# 09_FPGA_banks_5_6_7_8.net
KiCad netlist of a schematic drawn in Altium Designer
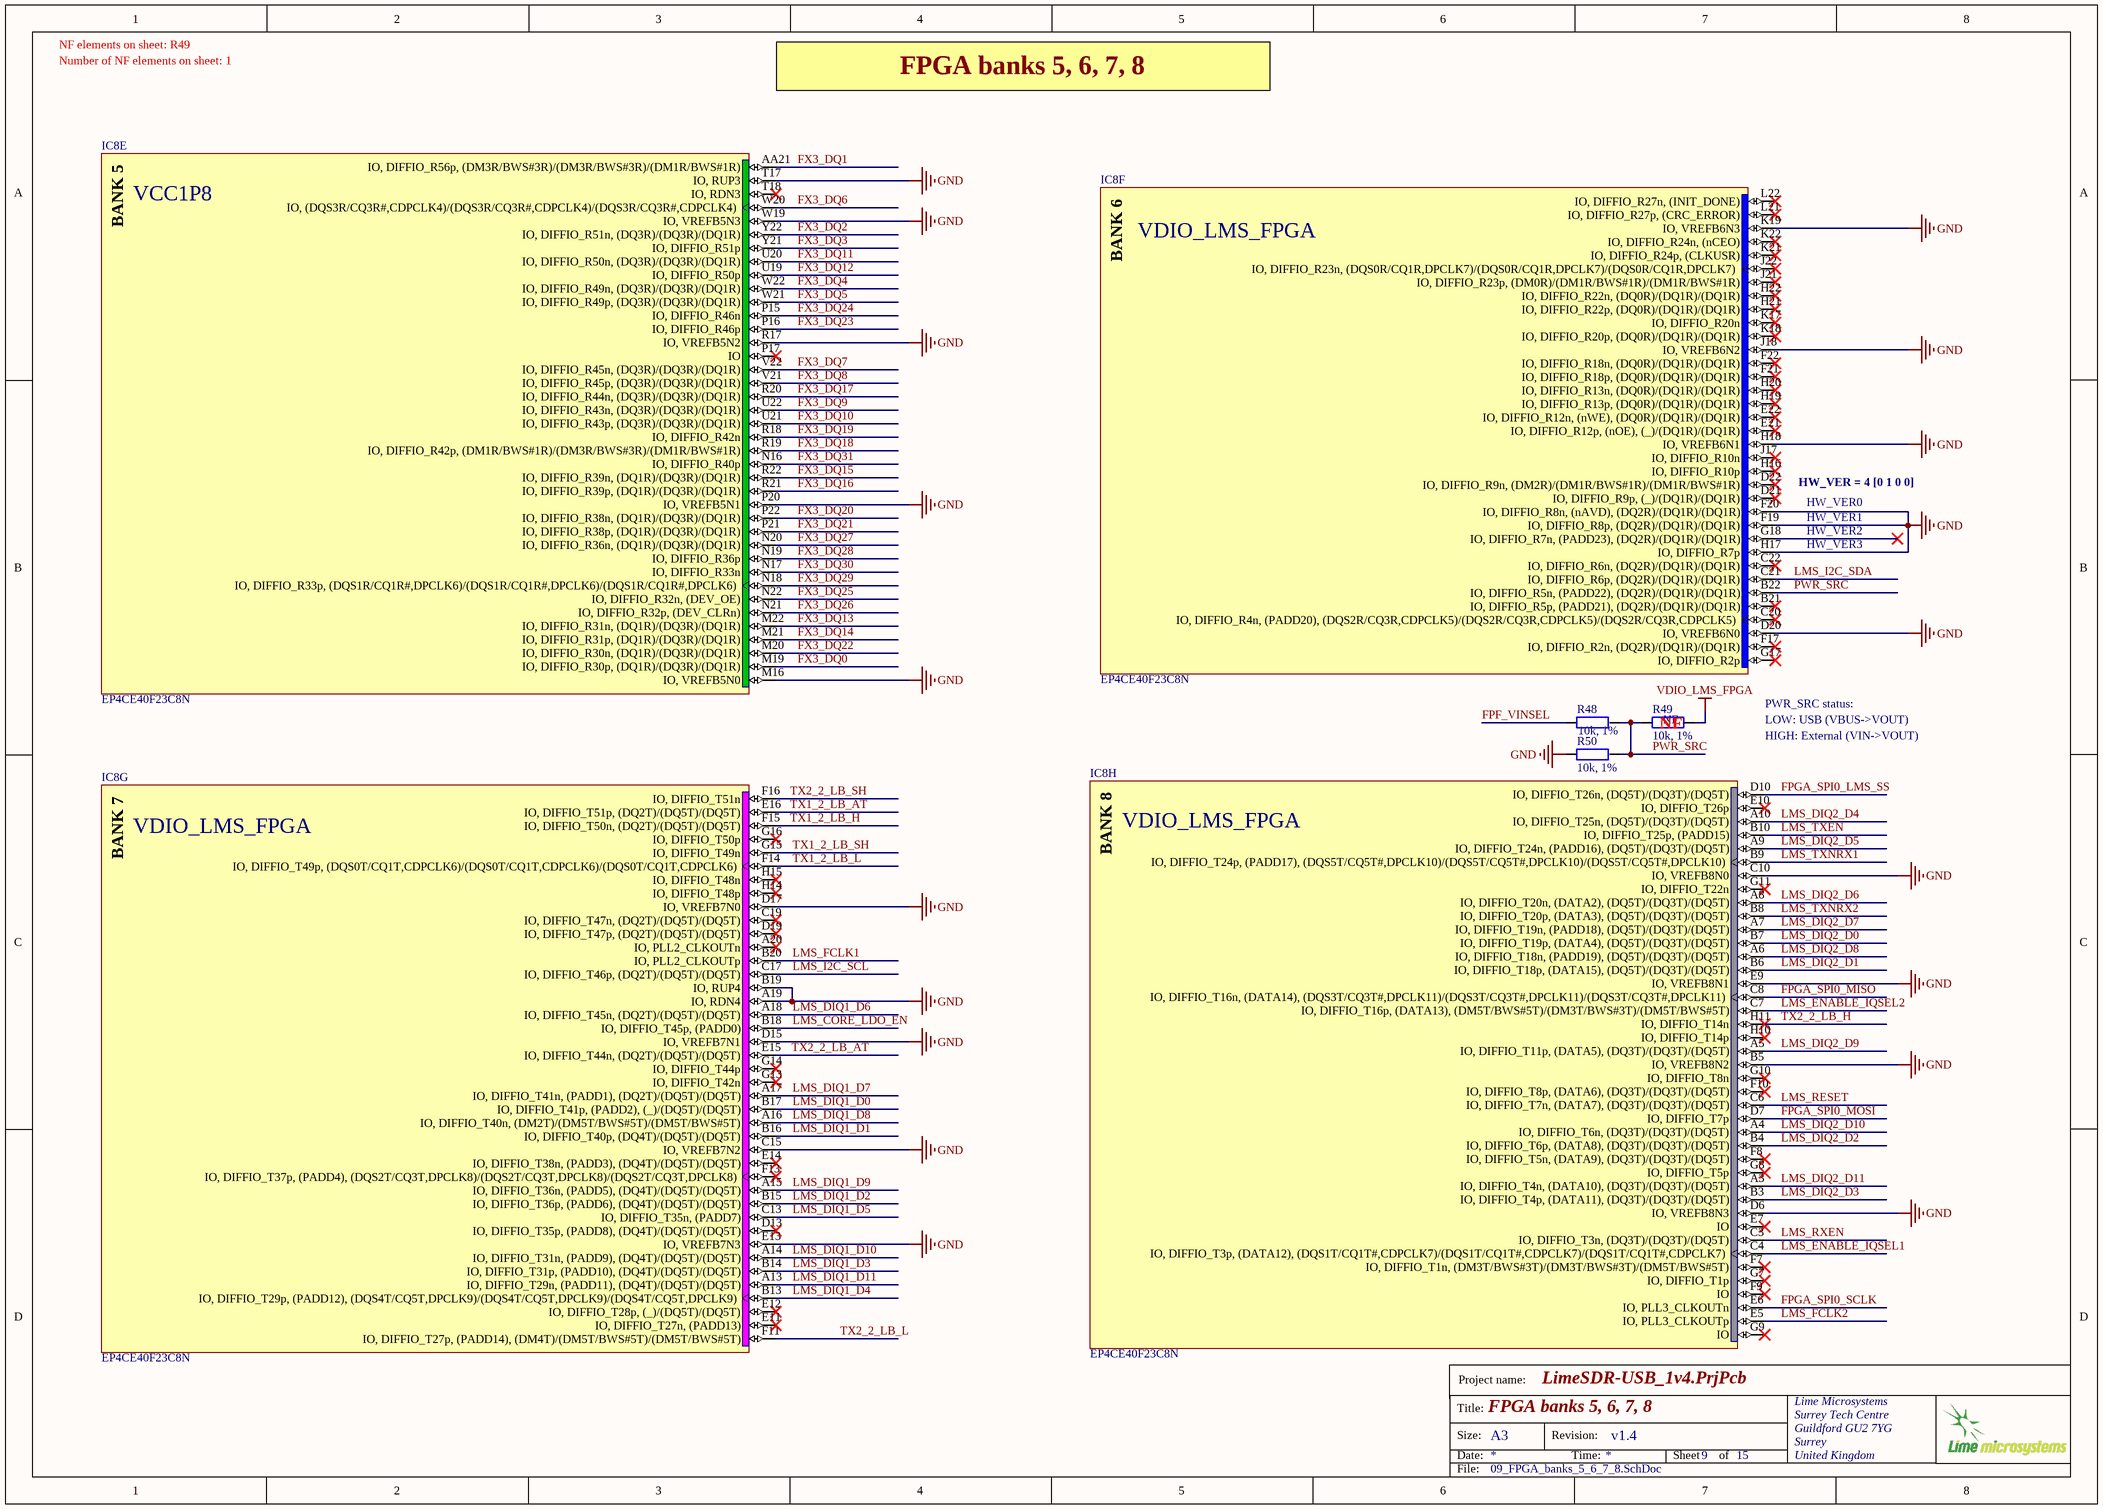
[diagram p0: 09_FPGA_banks_5_6_7_8.SchDoc]

(export (version "E")
  (design (tool "Eeschema 10.0.6"))
  (components
    (comp (ref "IC8")
      (value "EP4CE40F23C8N")
      (footprint "FBGA484_A-240")
      (description "IC FPGA 328 I/O 484FBGA")
      (fields (field (name "MANUFACTURER") "Altera"))
      (libsource (lib "LimeMicroAltiumLib_schLib") (part "EP4CE40F23C7N"))
    )
    (comp (ref "R48")
      (value "10k, 1%")
      (footprint "RES0402")
      (fields (field (name "MANUFACTURER") "Yageo") (field (name "TOLERANCE") "±1%"))
      (libsource (lib "LimeMicroAltiumLib_schLib") (part "Res_0402"))
    )
    (comp (ref "R49")
      (value "10k, 1%")
      (footprint "RES0402")
      (fields
        (field (name "ASSEMBLY INFO") "NF")
        (field (name "MANUFACTURER") "Yageo")
        (field (name "TOLERANCE") "±1%")
      )
      (libsource (lib "LimeMicroAltiumLib_schLib") (part "Res_0402"))
    )
    (comp (ref "R50")
      (value "10k, 1%")
      (footprint "RES0402")
      (fields (field (name "MANUFACTURER") "Yageo") (field (name "TOLERANCE") "±1%"))
      (libsource (lib "LimeMicroAltiumLib_schLib") (part "Res_0402"))
    )
  )
  (nets
    (net (code "1") (name "/FPF_VINSEL") (class "Default")
      (node (ref "R48") (pin "1") (pinfunction "1_1") (pintype "passive"))
    )
    (net (code "2") (name "/FPGA_SPI0_LMS_SS") (class "Default")
      (node (ref "IC8") (pin "D10") (pinfunction "IO,_DIFFIO_T26n,_(DQ5T)/(DQ3T)/(DQ5T)_D10") (pintype "bidirectional"))
    )
    (net (code "3") (name "/FPGA_SPI0_MISO") (class "Default")
      (node (ref "IC8") (pin "C8") (pinfunction "IO,_DIFFIO_T16n,_(DATA14),_(DQS3T/CQ3T#,DPCLK11)/(DQS3T/CQ3T#,DPCLK11)/(DQS3T/CQ3T#,DPCLK11)_C8") (pintype "bidirectional"))
    )
    (net (code "4") (name "/FPGA_SPI0_MOSI") (class "Default")
      (node (ref "IC8") (pin "D7") (pinfunction "IO,_DIFFIO_T7p_D7") (pintype "bidirectional"))
    )
    (net (code "5") (name "/FPGA_SPI0_SCLK") (class "Default")
      (node (ref "IC8") (pin "E6") (pinfunction "IO,_PLL3_CLKOUTn_E6") (pintype "bidirectional"))
    )
    (net (code "6") (name "/FX3_DQ0") (class "Default")
      (node (ref "IC8") (pin "M19") (pinfunction "IO,_DIFFIO_R30p,_(DQ1R)/(DQ3R)/(DQ1R)_M19") (pintype "bidirectional"))
    )
    (net (code "7") (name "/FX3_DQ1") (class "Default")
      (node (ref "IC8") (pin "AA21") (pinfunction "IO,_DIFFIO_R56p,_(DM3R/BWS#3R)/(DM3R/BWS#3R)/(DM1R/BWS#1R)_AA21") (pintype "bidirectional"))
    )
    (net (code "8") (name "/FX3_DQ2") (class "Default")
      (node (ref "IC8") (pin "Y22") (pinfunction "IO,_DIFFIO_R51n,_(DQ3R)/(DQ3R)/(DQ1R)_Y22") (pintype "bidirectional"))
    )
    (net (code "9") (name "/FX3_DQ3") (class "Default")
      (node (ref "IC8") (pin "Y21") (pinfunction "IO,_DIFFIO_R51p_Y21") (pintype "bidirectional"))
    )
    (net (code "10") (name "/FX3_DQ4") (class "Default")
      (node (ref "IC8") (pin "W22") (pinfunction "IO,_DIFFIO_R49n,_(DQ3R)/(DQ3R)/(DQ1R)_W22") (pintype "bidirectional"))
    )
    (net (code "11") (name "/FX3_DQ5") (class "Default")
      (node (ref "IC8") (pin "W21") (pinfunction "IO,_DIFFIO_R49p,_(DQ3R)/(DQ3R)/(DQ1R)_W21") (pintype "bidirectional"))
    )
    (net (code "12") (name "/FX3_DQ6") (class "Default")
      (node (ref "IC8") (pin "W20") (pinfunction "IO,_(DQS3R/CQ3R#,CDPCLK4)/(DQS3R/CQ3R#,CDPCLK4)/(DQS3R/CQ3R#,CDPCLK4)_W20") (pintype "bidirectional"))
    )
    (net (code "13") (name "/FX3_DQ7") (class "Default")
      (node (ref "IC8") (pin "V22") (pinfunction "IO,_DIFFIO_R45n,_(DQ3R)/(DQ3R)/(DQ1R)_V22") (pintype "bidirectional"))
    )
    (net (code "14") (name "/FX3_DQ8") (class "Default")
      (node (ref "IC8") (pin "V21") (pinfunction "IO,_DIFFIO_R45p,_(DQ3R)/(DQ3R)/(DQ1R)_V21") (pintype "bidirectional"))
    )
    (net (code "15") (name "/FX3_DQ9") (class "Default")
      (node (ref "IC8") (pin "U22") (pinfunction "IO,_DIFFIO_R43n,_(DQ3R)/(DQ3R)/(DQ1R)_U22") (pintype "bidirectional"))
    )
    (net (code "16") (name "/FX3_DQ10") (class "Default")
      (node (ref "IC8") (pin "U21") (pinfunction "IO,_DIFFIO_R43p,_(DQ3R)/(DQ3R)/(DQ1R)_U21") (pintype "bidirectional"))
    )
    (net (code "17") (name "/FX3_DQ11") (class "Default")
      (node (ref "IC8") (pin "U20") (pinfunction "IO,_DIFFIO_R50n,_(DQ3R)/(DQ3R)/(DQ1R)_U20") (pintype "bidirectional"))
    )
    (net (code "18") (name "/FX3_DQ12") (class "Default")
      (node (ref "IC8") (pin "U19") (pinfunction "IO,_DIFFIO_R50p_U19") (pintype "bidirectional"))
    )
    (net (code "19") (name "/FX3_DQ13") (class "Default")
      (node (ref "IC8") (pin "M22") (pinfunction "IO,_DIFFIO_R31n,_(DQ1R)/(DQ3R)/(DQ1R)_M22") (pintype "bidirectional"))
    )
    (net (code "20") (name "/FX3_DQ14") (class "Default")
      (node (ref "IC8") (pin "M21") (pinfunction "IO,_DIFFIO_R31p,_(DQ1R)/(DQ3R)/(DQ1R)_M21") (pintype "bidirectional"))
    )
    (net (code "21") (name "/FX3_DQ15") (class "Default")
      (node (ref "IC8") (pin "R22") (pinfunction "IO,_DIFFIO_R39n,_(DQ1R)/(DQ3R)/(DQ1R)_R22") (pintype "bidirectional"))
    )
    (net (code "22") (name "/FX3_DQ16") (class "Default")
      (node (ref "IC8") (pin "R21") (pinfunction "IO,_DIFFIO_R39p,_(DQ1R)/(DQ3R)/(DQ1R)_R21") (pintype "bidirectional"))
    )
    (net (code "23") (name "/FX3_DQ17") (class "Default")
      (node (ref "IC8") (pin "R20") (pinfunction "IO,_DIFFIO_R44n,_(DQ3R)/(DQ3R)/(DQ1R)_R20") (pintype "bidirectional"))
    )
    (net (code "24") (name "/FX3_DQ18") (class "Default")
      (node (ref "IC8") (pin "R19") (pinfunction "IO,_DIFFIO_R42p,_(DM1R/BWS#1R)/(DM3R/BWS#3R)/(DM1R/BWS#1R)_R19") (pintype "bidirectional"))
    )
    (net (code "25") (name "/FX3_DQ19") (class "Default")
      (node (ref "IC8") (pin "R18") (pinfunction "IO,_DIFFIO_R42n_R18") (pintype "bidirectional"))
    )
    (net (code "26") (name "/FX3_DQ20") (class "Default")
      (node (ref "IC8") (pin "P22") (pinfunction "IO,_DIFFIO_R38n,_(DQ1R)/(DQ3R)/(DQ1R)_P22") (pintype "bidirectional"))
    )
    (net (code "27") (name "/FX3_DQ21") (class "Default")
      (node (ref "IC8") (pin "P21") (pinfunction "IO,_DIFFIO_R38p,_(DQ1R)/(DQ3R)/(DQ1R)_P21") (pintype "bidirectional"))
    )
    (net (code "28") (name "/FX3_DQ22") (class "Default")
      (node (ref "IC8") (pin "M20") (pinfunction "IO,_DIFFIO_R30n,_(DQ1R)/(DQ3R)/(DQ1R)_M20") (pintype "bidirectional"))
    )
    (net (code "29") (name "/FX3_DQ23") (class "Default")
      (node (ref "IC8") (pin "P16") (pinfunction "IO,_DIFFIO_R46p_P16") (pintype "bidirectional"))
    )
    (net (code "30") (name "/FX3_DQ24") (class "Default")
      (node (ref "IC8") (pin "P15") (pinfunction "IO,_DIFFIO_R46n_P15") (pintype "bidirectional"))
    )
    (net (code "31") (name "/FX3_DQ25") (class "Default")
      (node (ref "IC8") (pin "N22") (pinfunction "IO,_DIFFIO_R32n,_(DEV_OE)_N22") (pintype "bidirectional"))
    )
    (net (code "32") (name "/FX3_DQ26") (class "Default")
      (node (ref "IC8") (pin "N21") (pinfunction "IO,_DIFFIO_R32p,_(DEV_CLRn)_N21") (pintype "bidirectional"))
    )
    (net (code "33") (name "/FX3_DQ27") (class "Default")
      (node (ref "IC8") (pin "N20") (pinfunction "IO,_DIFFIO_R36n,_(DQ1R)/(DQ3R)/(DQ1R)_N20") (pintype "bidirectional"))
    )
    (net (code "34") (name "/FX3_DQ28") (class "Default")
      (node (ref "IC8") (pin "N19") (pinfunction "IO,_DIFFIO_R36p_N19") (pintype "bidirectional"))
    )
    (net (code "35") (name "/FX3_DQ29") (class "Default")
      (node (ref "IC8") (pin "N18") (pinfunction "IO,_DIFFIO_R33p,_(DQS1R/CQ1R#,DPCLK6)/(DQS1R/CQ1R#,DPCLK6)/(DQS1R/CQ1R#,DPCLK6)_N18") (pintype "bidirectional"))
    )
    (net (code "36") (name "/FX3_DQ30") (class "Default")
      (node (ref "IC8") (pin "N17") (pinfunction "IO,_DIFFIO_R33n_N17") (pintype "bidirectional"))
    )
    (net (code "37") (name "/FX3_DQ31") (class "Default")
      (node (ref "IC8") (pin "N16") (pinfunction "IO,_DIFFIO_R40p_N16") (pintype "bidirectional"))
    )
    (net (code "38") (name "/LMS_CORE_LDO_EN") (class "Default")
      (node (ref "IC8") (pin "B18") (pinfunction "IO,_DIFFIO_T45p,_(PADD0)_B18") (pintype "bidirectional"))
    )
    (net (code "39") (name "/LMS_DIQ1_D0") (class "Default")
      (node (ref "IC8") (pin "B17") (pinfunction "IO,_DIFFIO_T41p,_(PADD2),_(_)/(DQ5T)/(DQ5T)_B17") (pintype "bidirectional"))
    )
    (net (code "40") (name "/LMS_DIQ1_D1") (class "Default")
      (node (ref "IC8") (pin "B16") (pinfunction "IO,_DIFFIO_T40p,_(DQ4T)/(DQ5T)/(DQ5T)_B16") (pintype "bidirectional"))
    )
    (net (code "41") (name "/LMS_DIQ1_D2") (class "Default")
      (node (ref "IC8") (pin "B15") (pinfunction "IO,_DIFFIO_T36p,_(PADD6),_(DQ4T)/(DQ5T)/(DQ5T)_B15") (pintype "bidirectional"))
    )
    (net (code "42") (name "/LMS_DIQ1_D3") (class "Default")
      (node (ref "IC8") (pin "B14") (pinfunction "IO,_DIFFIO_T31p,_(PADD10),_(DQ4T)/(DQ5T)/(DQ5T)_B14") (pintype "bidirectional"))
    )
    (net (code "43") (name "/LMS_DIQ1_D4") (class "Default")
      (node (ref "IC8") (pin "B13") (pinfunction "IO,_DIFFIO_T29p,_(PADD12),_(DQS4T/CQ5T,DPCLK9)/(DQS4T/CQ5T,DPCLK9)/(DQS4T/CQ5T,DPCLK9)_B13") (pintype "bidirectional"))
    )
    (net (code "44") (name "/LMS_DIQ1_D5") (class "Default")
      (node (ref "IC8") (pin "C13") (pinfunction "IO,_DIFFIO_T35n,_(PADD7)_C13") (pintype "bidirectional"))
    )
    (net (code "45") (name "/LMS_DIQ1_D6") (class "Default")
      (node (ref "IC8") (pin "A18") (pinfunction "IO,_DIFFIO_T45n,_(DQ2T)/(DQ5T)/(DQ5T)_A18") (pintype "bidirectional"))
    )
    (net (code "46") (name "/LMS_DIQ1_D7") (class "Default")
      (node (ref "IC8") (pin "A17") (pinfunction "IO,_DIFFIO_T41n,_(PADD1),_(DQ2T)/(DQ5T)/(DQ5T)_A17") (pintype "bidirectional"))
    )
    (net (code "47") (name "/LMS_DIQ1_D8") (class "Default")
      (node (ref "IC8") (pin "A16") (pinfunction "IO,_DIFFIO_T40n,_(DM2T)/(DM5T/BWS#5T)/(DM5T/BWS#5T)_A16") (pintype "bidirectional"))
    )
    (net (code "48") (name "/LMS_DIQ1_D9") (class "Default")
      (node (ref "IC8") (pin "A15") (pinfunction "IO,_DIFFIO_T36n,_(PADD5),_(DQ4T)/(DQ5T)/(DQ5T)_A15") (pintype "bidirectional"))
    )
    (net (code "49") (name "/LMS_DIQ1_D10") (class "Default")
      (node (ref "IC8") (pin "A14") (pinfunction "IO,_DIFFIO_T31n,_(PADD9),_(DQ4T)/(DQ5T)/(DQ5T)_A14") (pintype "bidirectional"))
    )
    (net (code "50") (name "/LMS_DIQ1_D11") (class "Default")
      (node (ref "IC8") (pin "A13") (pinfunction "IO,_DIFFIO_T29n,_(PADD11),_(DQ4T)/(DQ5T)/(DQ5T)_A13") (pintype "bidirectional"))
    )
    (net (code "51") (name "/LMS_DIQ2_D0") (class "Default")
      (node (ref "IC8") (pin "B7") (pinfunction "IO,_DIFFIO_T19p,_(DATA4),_(DQ5T)/(DQ3T)/(DQ5T)_B7") (pintype "bidirectional"))
    )
    (net (code "52") (name "/LMS_DIQ2_D1") (class "Default")
      (node (ref "IC8") (pin "B6") (pinfunction "IO,_DIFFIO_T18p,_(DATA15),_(DQ5T)/(DQ3T)/(DQ5T)_B6") (pintype "bidirectional"))
    )
    (net (code "53") (name "/LMS_DIQ2_D2") (class "Default")
      (node (ref "IC8") (pin "B4") (pinfunction "IO,_DIFFIO_T6p,_(DATA8),_(DQ3T)/(DQ3T)/(DQ5T)_B4") (pintype "bidirectional"))
    )
    (net (code "54") (name "/LMS_DIQ2_D3") (class "Default")
      (node (ref "IC8") (pin "B3") (pinfunction "IO,_DIFFIO_T4p,_(DATA11),_(DQ3T)/(DQ3T)/(DQ5T)_B3") (pintype "bidirectional"))
    )
    (net (code "55") (name "/LMS_DIQ2_D4") (class "Default")
      (node (ref "IC8") (pin "A10") (pinfunction "IO,_DIFFIO_T25n,_(DQ5T)/(DQ3T)/(DQ5T)_A10") (pintype "bidirectional"))
    )
    (net (code "56") (name "/LMS_DIQ2_D5") (class "Default")
      (node (ref "IC8") (pin "A9") (pinfunction "IO,_DIFFIO_T24n,_(PADD16),_(DQ5T)/(DQ3T)/(DQ5T)_A9") (pintype "bidirectional"))
    )
    (net (code "57") (name "/LMS_DIQ2_D6") (class "Default")
      (node (ref "IC8") (pin "A8") (pinfunction "IO,_DIFFIO_T20n,_(DATA2),_(DQ5T)/(DQ3T)/(DQ5T)_A8") (pintype "bidirectional"))
    )
    (net (code "58") (name "/LMS_DIQ2_D7") (class "Default")
      (node (ref "IC8") (pin "A7") (pinfunction "IO,_DIFFIO_T19n,_(PADD18),_(DQ5T)/(DQ3T)/(DQ5T)_A7") (pintype "bidirectional"))
    )
    (net (code "59") (name "/LMS_DIQ2_D8") (class "Default")
      (node (ref "IC8") (pin "A6") (pinfunction "IO,_DIFFIO_T18n,_(PADD19),_(DQ5T)/(DQ3T)/(DQ5T)_A6") (pintype "bidirectional"))
    )
    (net (code "60") (name "/LMS_DIQ2_D9") (class "Default")
      (node (ref "IC8") (pin "A5") (pinfunction "IO,_DIFFIO_T11p,_(DATA5),_(DQ3T)/(DQ3T)/(DQ5T)_A5") (pintype "bidirectional"))
    )
    (net (code "61") (name "/LMS_DIQ2_D10") (class "Default")
      (node (ref "IC8") (pin "A4") (pinfunction "IO,_DIFFIO_T6n,_(DQ3T)/(DQ3T)/(DQ5T)_A4") (pintype "bidirectional"))
    )
    (net (code "62") (name "/LMS_DIQ2_D11") (class "Default")
      (node (ref "IC8") (pin "A3") (pinfunction "IO,_DIFFIO_T4n,_(DATA10),_(DQ3T)/(DQ3T)/(DQ5T)_A3") (pintype "bidirectional"))
    )
    (net (code "63") (name "/LMS_ENABLE_IQSEL1") (class "Default")
      (node (ref "IC8") (pin "C4") (pinfunction "IO,_DIFFIO_T3p,_(DATA12),_(DQS1T/CQ1T#,CDPCLK7)/(DQS1T/CQ1T#,CDPCLK7)/(DQS1T/CQ1T#,CDPCLK7)_C4") (pintype "bidirectional"))
    )
    (net (code "64") (name "/LMS_ENABLE_IQSEL2") (class "Default")
      (node (ref "IC8") (pin "C7") (pinfunction "IO,_DIFFIO_T16p,_(DATA13),_(DM5T/BWS#5T)/(DM3T/BWS#3T)/(DM5T/BWS#5T)_C7") (pintype "bidirectional"))
    )
    (net (code "65") (name "/LMS_FCLK1") (class "Default")
      (node (ref "IC8") (pin "B20") (pinfunction "IO,_PLL2_CLKOUTp_B20") (pintype "bidirectional"))
    )
    (net (code "66") (name "/LMS_FCLK2") (class "Default")
      (node (ref "IC8") (pin "E5") (pinfunction "IO,_PLL3_CLKOUTp_E5") (pintype "bidirectional"))
    )
    (net (code "67") (name "/LMS_I2C_SCL") (class "Default")
      (node (ref "IC8") (pin "C17") (pinfunction "IO,_DIFFIO_T46p,_(DQ2T)/(DQ5T)/(DQ5T)_C17") (pintype "bidirectional"))
    )
    (net (code "68") (name "/LMS_I2C_SDA") (class "Default")
      (node (ref "IC8") (pin "C21") (pinfunction "IO,_DIFFIO_R6p,_(DQ2R)/(DQ1R)/(DQ1R)_C21") (pintype "bidirectional"))
    )
    (net (code "69") (name "/LMS_RESET") (class "Default")
      (node (ref "IC8") (pin "C6") (pinfunction "IO,_DIFFIO_T7n,_(DATA7),_(DQ3T)/(DQ3T)/(DQ5T)_C6") (pintype "bidirectional"))
    )
    (net (code "70") (name "/LMS_RXEN") (class "Default")
      (node (ref "IC8") (pin "C3") (pinfunction "IO,_DIFFIO_T3n,_(DQ3T)/(DQ3T)/(DQ5T)_C3") (pintype "bidirectional"))
    )
    (net (code "71") (name "/LMS_TXEN") (class "Default")
      (node (ref "IC8") (pin "B10") (pinfunction "IO,_DIFFIO_T25p,_(PADD15)_B10") (pintype "bidirectional"))
    )
    (net (code "72") (name "/LMS_TXNRX1") (class "Default")
      (node (ref "IC8") (pin "B9") (pinfunction "IO,_DIFFIO_T24p,_(PADD17),_(DQS5T/CQ5T#,DPCLK10)/(DQS5T/CQ5T#,DPCLK10)/(DQS5T/CQ5T#,DPCLK10)_B9") (pintype "bidirectional"))
    )
    (net (code "73") (name "/LMS_TXNRX2") (class "Default")
      (node (ref "IC8") (pin "B8") (pinfunction "IO,_DIFFIO_T20p,_(DATA3),_(DQ5T)/(DQ3T)/(DQ5T)_B8") (pintype "bidirectional"))
    )
    (net (code "74") (name "/PWR_SRC") (class "Default")
      (node (ref "IC8") (pin "B22") (pinfunction "IO,_DIFFIO_R5n,_(PADD22),_(DQ2R)/(DQ1R)/(DQ1R)_B22") (pintype "bidirectional"))
      (node (ref "R48") (pin "2") (pinfunction "2_2") (pintype "passive"))
      (node (ref "R49") (pin "1") (pinfunction "1_1") (pintype "passive"))
      (node (ref "R50") (pin "2") (pinfunction "2_2") (pintype "passive"))
    )
    (net (code "75") (name "/TX1_2_LB_AT") (class "Default")
      (node (ref "IC8") (pin "E16") (pinfunction "IO,_DIFFIO_T51p,_(DQ2T)/(DQ5T)/(DQ5T)_E16") (pintype "bidirectional"))
    )
    (net (code "76") (name "/TX1_2_LB_H") (class "Default")
      (node (ref "IC8") (pin "F15") (pinfunction "IO,_DIFFIO_T50n,_(DQ2T)/(DQ5T)/(DQ5T)_F15") (pintype "bidirectional"))
    )
    (net (code "77") (name "/TX1_2_LB_L") (class "Default")
      (node (ref "IC8") (pin "F14") (pinfunction "IO,_DIFFIO_T49p,_(DQS0T/CQ1T,CDPCLK6)/(DQS0T/CQ1T,CDPCLK6)/(DQS0T/CQ1T,CDPCLK6)_F14") (pintype "bidirectional"))
    )
    (net (code "78") (name "/TX1_2_LB_SH") (class "Default")
      (node (ref "IC8") (pin "G15") (pinfunction "IO,_DIFFIO_T49n_G15") (pintype "bidirectional"))
    )
    (net (code "79") (name "/TX2_2_LB_AT") (class "Default")
      (node (ref "IC8") (pin "E15") (pinfunction "IO,_DIFFIO_T44n,_(DQ2T)/(DQ5T)/(DQ5T)_E15") (pintype "bidirectional"))
    )
    (net (code "80") (name "/TX2_2_LB_H") (class "Default")
      (node (ref "IC8") (pin "H11") (pinfunction "IO,_DIFFIO_T14n_H11") (pintype "bidirectional+no_connect"))
    )
    (net (code "81") (name "/TX2_2_LB_L") (class "Default")
      (node (ref "IC8") (pin "F11") (pinfunction "IO,_DIFFIO_T27p,_(PADD14),_(DM4T)/(DM5T/BWS#5T)/(DM5T/BWS#5T)_F11") (pintype "bidirectional"))
    )
    (net (code "82") (name "/TX2_2_LB_SH") (class "Default")
      (node (ref "IC8") (pin "F16") (pinfunction "IO,_DIFFIO_T51n_F16") (pintype "bidirectional"))
    )
    (net (code "83") (name "GND") (class "Default")
      (node (ref "IC8") (pin "A19") (pinfunction "IO,_RDN4_A19") (pintype "bidirectional"))
      (node (ref "IC8") (pin "B19") (pinfunction "IO,_RUP4_B19") (pintype "bidirectional"))
      (node (ref "IC8") (pin "B5") (pinfunction "IO,_VREFB8N2_B5") (pintype "bidirectional"))
      (node (ref "IC8") (pin "C10") (pinfunction "IO,_VREFB8N0_C10") (pintype "bidirectional"))
      (node (ref "IC8") (pin "C15") (pinfunction "IO,_VREFB7N2_C15") (pintype "bidirectional"))
      (node (ref "IC8") (pin "D15") (pinfunction "IO,_VREFB7N1_D15") (pintype "bidirectional"))
      (node (ref "IC8") (pin "D17") (pinfunction "IO,_VREFB7N0_D17") (pintype "bidirectional"))
      (node (ref "IC8") (pin "D20") (pinfunction "IO,_VREFB6N0_D20") (pintype "bidirectional"))
      (node (ref "IC8") (pin "D6") (pinfunction "IO,_VREFB8N3_D6") (pintype "bidirectional"))
      (node (ref "IC8") (pin "E13") (pinfunction "IO,_VREFB7N3_E13") (pintype "bidirectional"))
      (node (ref "IC8") (pin "E9") (pinfunction "IO,_VREFB8N1_E9") (pintype "bidirectional"))
      (node (ref "IC8") (pin "F19") (pinfunction "IO,_DIFFIO_R8p,_(DQ2R)/(DQ1R)/(DQ1R)_F19") (pintype "bidirectional"))
      (node (ref "IC8") (pin "F20") (pinfunction "IO,_DIFFIO_R8n,_(nAVD),_(DQ2R)/(DQ1R)/(DQ1R)_F20") (pintype "bidirectional"))
      (node (ref "IC8") (pin "H17") (pinfunction "IO,_DIFFIO_R7p_H17") (pintype "bidirectional"))
      (node (ref "IC8") (pin "H18") (pinfunction "IO,_VREFB6N1_H18") (pintype "bidirectional"))
      (node (ref "IC8") (pin "J18") (pinfunction "IO,_VREFB6N2_J18") (pintype "bidirectional"))
      (node (ref "IC8") (pin "K19") (pinfunction "IO,_VREFB6N3_K19") (pintype "bidirectional"))
      (node (ref "IC8") (pin "M16") (pinfunction "IO,_VREFB5N0_M16") (pintype "bidirectional"))
      (node (ref "IC8") (pin "P20") (pinfunction "IO,_VREFB5N1_P20") (pintype "bidirectional"))
      (node (ref "IC8") (pin "R17") (pinfunction "IO,_VREFB5N2_R17") (pintype "bidirectional"))
      (node (ref "IC8") (pin "T17") (pinfunction "IO,_RUP3_T17") (pintype "bidirectional"))
      (node (ref "IC8") (pin "W19") (pinfunction "IO,_VREFB5N3_W19") (pintype "bidirectional"))
      (node (ref "R50") (pin "1") (pinfunction "1_1") (pintype "passive"))
    )
    (net (code "84") (name "VDIO_LMS_FPGA") (class "Default")
      (node (ref "R49") (pin "2") (pinfunction "2_2") (pintype "passive"))
    )
    (net (code "85") (name "unconnected-(IC8E-IO,_RDN3-PadT18)") (class "Default")
      (node (ref "IC8") (pin "T18") (pinfunction "IO,_RDN3_T18") (pintype "bidirectional+no_connect"))
    )
    (net (code "86") (name "unconnected-(IC8E-IO-PadP17)") (class "Default")
      (node (ref "IC8") (pin "P17") (pinfunction "IO_P17") (pintype "bidirectional+no_connect"))
    )
    (net (code "87") (name "unconnected-(IC8F-IO,_DIFFIO_R2n,_(DQ2R){slash}(DQ1R){slash}(DQ1R)-PadF17)") (class "Default")
      (node (ref "IC8") (pin "F17") (pinfunction "IO,_DIFFIO_R2n,_(DQ2R)/(DQ1R)/(DQ1R)_F17") (pintype "bidirectional+no_connect"))
    )
    (net (code "88") (name "unconnected-(IC8F-IO,_DIFFIO_R2p-PadG17)") (class "Default")
      (node (ref "IC8") (pin "G17") (pinfunction "IO,_DIFFIO_R2p_G17") (pintype "bidirectional+no_connect"))
    )
    (net (code "89") (name "unconnected-(IC8F-IO,_DIFFIO_R4n,_(PADD20),_(DQS2R{slash}CQ3R,CDPCLK5){slash}(DQS2R{slash}CQ3R,CDPCLK5){slash}(DQS2R{slash}CQ3R,CDPCLK5)-PadC20)") (class "Default")
      (node (ref "IC8") (pin "C20") (pinfunction "IO,_DIFFIO_R4n,_(PADD20),_(DQS2R/CQ3R,CDPCLK5)/(DQS2R/CQ3R,CDPCLK5)/(DQS2R/CQ3R,CDPCLK5)_C20") (pintype "bidirectional+no_connect"))
    )
    (net (code "90") (name "unconnected-(IC8F-IO,_DIFFIO_R5p,_(PADD21),_(DQ2R){slash}(DQ1R){slash}(DQ1R)-PadB21)") (class "Default")
      (node (ref "IC8") (pin "B21") (pinfunction "IO,_DIFFIO_R5p,_(PADD21),_(DQ2R)/(DQ1R)/(DQ1R)_B21") (pintype "bidirectional+no_connect"))
    )
    (net (code "91") (name "unconnected-(IC8F-IO,_DIFFIO_R6n,_(DQ2R){slash}(DQ1R){slash}(DQ1R)-PadC22)") (class "Default")
      (node (ref "IC8") (pin "C22") (pinfunction "IO,_DIFFIO_R6n,_(DQ2R)/(DQ1R)/(DQ1R)_C22") (pintype "bidirectional+no_connect"))
    )
    (net (code "92") (name "unconnected-(IC8F-IO,_DIFFIO_R7n,_(PADD23),_(DQ2R){slash}(DQ1R){slash}(DQ1R)-PadG18)") (class "Default")
      (node (ref "IC8") (pin "G18") (pinfunction "IO,_DIFFIO_R7n,_(PADD23),_(DQ2R)/(DQ1R)/(DQ1R)_G18") (pintype "bidirectional+no_connect"))
    )
    (net (code "93") (name "unconnected-(IC8F-IO,_DIFFIO_R9n,_(DM2R){slash}(DM1R{slash}BWS#1R){slash}(DM1R{slash}BWS#1R)-PadD22)") (class "Default")
      (node (ref "IC8") (pin "D22") (pinfunction "IO,_DIFFIO_R9n,_(DM2R)/(DM1R/BWS#1R)/(DM1R/BWS#1R)_D22") (pintype "bidirectional+no_connect"))
    )
    (net (code "94") (name "unconnected-(IC8F-IO,_DIFFIO_R9p,_(_){slash}(DQ1R){slash}(DQ1R)-PadD21)") (class "Default")
      (node (ref "IC8") (pin "D21") (pinfunction "IO,_DIFFIO_R9p,_(_)/(DQ1R)/(DQ1R)_D21") (pintype "bidirectional+no_connect"))
    )
    (net (code "95") (name "unconnected-(IC8F-IO,_DIFFIO_R10n-PadJ17)") (class "Default")
      (node (ref "IC8") (pin "J17") (pinfunction "IO,_DIFFIO_R10n_J17") (pintype "bidirectional+no_connect"))
    )
    (net (code "96") (name "unconnected-(IC8F-IO,_DIFFIO_R10p-PadH16)") (class "Default")
      (node (ref "IC8") (pin "H16") (pinfunction "IO,_DIFFIO_R10p_H16") (pintype "bidirectional+no_connect"))
    )
    (net (code "97") (name "unconnected-(IC8F-IO,_DIFFIO_R12n,_(nWE),_(DQ0R){slash}(DQ1R){slash}(DQ1R)-PadE22)") (class "Default")
      (node (ref "IC8") (pin "E22") (pinfunction "IO,_DIFFIO_R12n,_(nWE),_(DQ0R)/(DQ1R)/(DQ1R)_E22") (pintype "bidirectional+no_connect"))
    )
    (net (code "98") (name "unconnected-(IC8F-IO,_DIFFIO_R12p,_(nOE),_(_){slash}(DQ1R){slash}(DQ1R)-PadE21)") (class "Default")
      (node (ref "IC8") (pin "E21") (pinfunction "IO,_DIFFIO_R12p,_(nOE),_(_)/(DQ1R)/(DQ1R)_E21") (pintype "bidirectional+no_connect"))
    )
    (net (code "99") (name "unconnected-(IC8F-IO,_DIFFIO_R13n,_(DQ0R){slash}(DQ1R){slash}(DQ1R)-PadH20)") (class "Default")
      (node (ref "IC8") (pin "H20") (pinfunction "IO,_DIFFIO_R13n,_(DQ0R)/(DQ1R)/(DQ1R)_H20") (pintype "bidirectional+no_connect"))
    )
    (net (code "100") (name "unconnected-(IC8F-IO,_DIFFIO_R13p,_(DQ0R){slash}(DQ1R){slash}(DQ1R)-PadH19)") (class "Default")
      (node (ref "IC8") (pin "H19") (pinfunction "IO,_DIFFIO_R13p,_(DQ0R)/(DQ1R)/(DQ1R)_H19") (pintype "bidirectional+no_connect"))
    )
    (net (code "101") (name "unconnected-(IC8F-IO,_DIFFIO_R18n,_(DQ0R){slash}(DQ1R){slash}(DQ1R)-PadF22)") (class "Default")
      (node (ref "IC8") (pin "F22") (pinfunction "IO,_DIFFIO_R18n,_(DQ0R)/(DQ1R)/(DQ1R)_F22") (pintype "bidirectional+no_connect"))
    )
    (net (code "102") (name "unconnected-(IC8F-IO,_DIFFIO_R18p,_(DQ0R){slash}(DQ1R){slash}(DQ1R)-PadF21)") (class "Default")
      (node (ref "IC8") (pin "F21") (pinfunction "IO,_DIFFIO_R18p,_(DQ0R)/(DQ1R)/(DQ1R)_F21") (pintype "bidirectional+no_connect"))
    )
    (net (code "103") (name "unconnected-(IC8F-IO,_DIFFIO_R20n-PadK17)") (class "Default")
      (node (ref "IC8") (pin "K17") (pinfunction "IO,_DIFFIO_R20n_K17") (pintype "bidirectional+no_connect"))
    )
    (net (code "104") (name "unconnected-(IC8F-IO,_DIFFIO_R20p,_(DQ0R){slash}(DQ1R){slash}(DQ1R)-PadK18)") (class "Default")
      (node (ref "IC8") (pin "K18") (pinfunction "IO,_DIFFIO_R20p,_(DQ0R)/(DQ1R)/(DQ1R)_K18") (pintype "bidirectional+no_connect"))
    )
    (net (code "105") (name "unconnected-(IC8F-IO,_DIFFIO_R22n,_(DQ0R){slash}(DQ1R){slash}(DQ1R)-PadH22)") (class "Default")
      (node (ref "IC8") (pin "H22") (pinfunction "IO,_DIFFIO_R22n,_(DQ0R)/(DQ1R)/(DQ1R)_H22") (pintype "bidirectional+no_connect"))
    )
    (net (code "106") (name "unconnected-(IC8F-IO,_DIFFIO_R22p,_(DQ0R){slash}(DQ1R){slash}(DQ1R)-PadH21)") (class "Default")
      (node (ref "IC8") (pin "H21") (pinfunction "IO,_DIFFIO_R22p,_(DQ0R)/(DQ1R)/(DQ1R)_H21") (pintype "bidirectional+no_connect"))
    )
    (net (code "107") (name "unconnected-(IC8F-IO,_DIFFIO_R23n,_(DQS0R{slash}CQ1R,DPCLK7){slash}(DQS0R{slash}CQ1R,DPCLK7){slash}(DQS0R{slash}CQ1R,DPCLK7)-PadJ22)") (class "Default")
      (node (ref "IC8") (pin "J22") (pinfunction "IO,_DIFFIO_R23n,_(DQS0R/CQ1R,DPCLK7)/(DQS0R/CQ1R,DPCLK7)/(DQS0R/CQ1R,DPCLK7)_J22") (pintype "bidirectional+no_connect"))
    )
    (net (code "108") (name "unconnected-(IC8F-IO,_DIFFIO_R23p,_(DM0R){slash}(DM1R{slash}BWS#1R){slash}(DM1R{slash}BWS#1R)-PadJ21)") (class "Default")
      (node (ref "IC8") (pin "J21") (pinfunction "IO,_DIFFIO_R23p,_(DM0R)/(DM1R/BWS#1R)/(DM1R/BWS#1R)_J21") (pintype "bidirectional+no_connect"))
    )
    (net (code "109") (name "unconnected-(IC8F-IO,_DIFFIO_R24n,_(nCEO)-PadK22)") (class "Default")
      (node (ref "IC8") (pin "K22") (pinfunction "IO,_DIFFIO_R24n,_(nCEO)_K22") (pintype "bidirectional+no_connect"))
    )
    (net (code "110") (name "unconnected-(IC8F-IO,_DIFFIO_R24p,_(CLKUSR)-PadK21)") (class "Default")
      (node (ref "IC8") (pin "K21") (pinfunction "IO,_DIFFIO_R24p,_(CLKUSR)_K21") (pintype "bidirectional+no_connect"))
    )
    (net (code "111") (name "unconnected-(IC8F-IO,_DIFFIO_R27n,_(INIT_DONE)-PadL22)") (class "Default")
      (node (ref "IC8") (pin "L22") (pinfunction "IO,_DIFFIO_R27n,_(INIT_DONE)_L22") (pintype "bidirectional+no_connect"))
    )
    (net (code "112") (name "unconnected-(IC8F-IO,_DIFFIO_R27p,_(CRC_ERROR)-PadL21)") (class "Default")
      (node (ref "IC8") (pin "L21") (pinfunction "IO,_DIFFIO_R27p,_(CRC_ERROR)_L21") (pintype "bidirectional+no_connect"))
    )
    (net (code "113") (name "unconnected-(IC8G-IO,_DIFFIO_T27n,_(PADD13)-PadE11)") (class "Default")
      (node (ref "IC8") (pin "E11") (pinfunction "IO,_DIFFIO_T27n,_(PADD13)_E11") (pintype "bidirectional+no_connect"))
    )
    (net (code "114") (name "unconnected-(IC8G-IO,_DIFFIO_T28p,_(_){slash}(DQ5T){slash}(DQ5T)-PadE12)") (class "Default")
      (node (ref "IC8") (pin "E12") (pinfunction "IO,_DIFFIO_T28p,_(_)/(DQ5T)/(DQ5T)_E12") (pintype "bidirectional+no_connect"))
    )
    (net (code "115") (name "unconnected-(IC8G-IO,_DIFFIO_T35p,_(PADD8),_(DQ4T){slash}(DQ5T){slash}(DQ5T)-PadD13)") (class "Default")
      (node (ref "IC8") (pin "D13") (pinfunction "IO,_DIFFIO_T35p,_(PADD8),_(DQ4T)/(DQ5T)/(DQ5T)_D13") (pintype "bidirectional+no_connect"))
    )
    (net (code "116") (name "unconnected-(IC8G-IO,_DIFFIO_T37p,_(PADD4),_(DQS2T{slash}CQ3T,DPCLK8){slash}(DQS2T{slash}CQ3T,DPCLK8){slash}(DQS2T{slash}CQ3T,DPCLK8)-PadF13)") (class "Default")
      (node (ref "IC8") (pin "F13") (pinfunction "IO,_DIFFIO_T37p,_(PADD4),_(DQS2T/CQ3T,DPCLK8)/(DQS2T/CQ3T,DPCLK8)/(DQS2T/CQ3T,DPCLK8)_F13") (pintype "bidirectional+no_connect"))
    )
    (net (code "117") (name "unconnected-(IC8G-IO,_DIFFIO_T38n,_(PADD3),_(DQ4T){slash}(DQ5T){slash}(DQ5T)-PadE14)") (class "Default")
      (node (ref "IC8") (pin "E14") (pinfunction "IO,_DIFFIO_T38n,_(PADD3),_(DQ4T)/(DQ5T)/(DQ5T)_E14") (pintype "bidirectional+no_connect"))
    )
    (net (code "118") (name "unconnected-(IC8G-IO,_DIFFIO_T42n-PadG13)") (class "Default")
      (node (ref "IC8") (pin "G13") (pinfunction "IO,_DIFFIO_T42n_G13") (pintype "bidirectional+no_connect"))
    )
    (net (code "119") (name "unconnected-(IC8G-IO,_DIFFIO_T44p-PadG14)") (class "Default")
      (node (ref "IC8") (pin "G14") (pinfunction "IO,_DIFFIO_T44p_G14") (pintype "bidirectional+no_connect"))
    )
    (net (code "120") (name "unconnected-(IC8G-IO,_DIFFIO_T47n,_(DQ2T){slash}(DQ5T){slash}(DQ5T)-PadC19)") (class "Default")
      (node (ref "IC8") (pin "C19") (pinfunction "IO,_DIFFIO_T47n,_(DQ2T)/(DQ5T)/(DQ5T)_C19") (pintype "bidirectional+no_connect"))
    )
    (net (code "121") (name "unconnected-(IC8G-IO,_DIFFIO_T47p,_(DQ2T){slash}(DQ5T){slash}(DQ5T)-PadD19)") (class "Default")
      (node (ref "IC8") (pin "D19") (pinfunction "IO,_DIFFIO_T47p,_(DQ2T)/(DQ5T)/(DQ5T)_D19") (pintype "bidirectional+no_connect"))
    )
    (net (code "122") (name "unconnected-(IC8G-IO,_DIFFIO_T48n-PadH15)") (class "Default")
      (node (ref "IC8") (pin "H15") (pinfunction "IO,_DIFFIO_T48n_H15") (pintype "bidirectional+no_connect"))
    )
    (net (code "123") (name "unconnected-(IC8G-IO,_DIFFIO_T48p-PadH14)") (class "Default")
      (node (ref "IC8") (pin "H14") (pinfunction "IO,_DIFFIO_T48p_H14") (pintype "bidirectional+no_connect"))
    )
    (net (code "124") (name "unconnected-(IC8G-IO,_DIFFIO_T50p-PadG16)") (class "Default")
      (node (ref "IC8") (pin "G16") (pinfunction "IO,_DIFFIO_T50p_G16") (pintype "bidirectional+no_connect"))
    )
    (net (code "125") (name "unconnected-(IC8G-IO,_PLL2_CLKOUTn-PadA20)") (class "Default")
      (node (ref "IC8") (pin "A20") (pinfunction "IO,_PLL2_CLKOUTn_A20") (pintype "bidirectional+no_connect"))
    )
    (net (code "126") (name "unconnected-(IC8H-IO,_DIFFIO_T1n,_(DM3T{slash}BWS#3T){slash}(DM3T{slash}BWS#3T){slash}(DM5T{slash}BWS#5T)-PadF7)") (class "Default")
      (node (ref "IC8") (pin "F7") (pinfunction "IO,_DIFFIO_T1n,_(DM3T/BWS#3T)/(DM3T/BWS#3T)/(DM5T/BWS#5T)_F7") (pintype "bidirectional+no_connect"))
    )
    (net (code "127") (name "unconnected-(IC8H-IO,_DIFFIO_T1p-PadG7)") (class "Default")
      (node (ref "IC8") (pin "G7") (pinfunction "IO,_DIFFIO_T1p_G7") (pintype "bidirectional+no_connect"))
    )
    (net (code "128") (name "unconnected-(IC8H-IO,_DIFFIO_T5n,_(DATA9),_(DQ3T){slash}(DQ3T){slash}(DQ5T)-PadF8)") (class "Default")
      (node (ref "IC8") (pin "F8") (pinfunction "IO,_DIFFIO_T5n,_(DATA9),_(DQ3T)/(DQ3T)/(DQ5T)_F8") (pintype "bidirectional+no_connect"))
    )
    (net (code "129") (name "unconnected-(IC8H-IO,_DIFFIO_T5p-PadG8)") (class "Default")
      (node (ref "IC8") (pin "G8") (pinfunction "IO,_DIFFIO_T5p_G8") (pintype "bidirectional+no_connect"))
    )
    (net (code "130") (name "unconnected-(IC8H-IO,_DIFFIO_T8n-PadG10)") (class "Default")
      (node (ref "IC8") (pin "G10") (pinfunction "IO,_DIFFIO_T8n_G10") (pintype "bidirectional+no_connect"))
    )
    (net (code "131") (name "unconnected-(IC8H-IO,_DIFFIO_T8p,_(DATA6),_(DQ3T){slash}(DQ3T){slash}(DQ5T)-PadF10)") (class "Default")
      (node (ref "IC8") (pin "F10") (pinfunction "IO,_DIFFIO_T8p,_(DATA6),_(DQ3T)/(DQ3T)/(DQ5T)_F10") (pintype "bidirectional+no_connect"))
    )
    (net (code "132") (name "unconnected-(IC8H-IO,_DIFFIO_T14p-PadH10)") (class "Default")
      (node (ref "IC8") (pin "H10") (pinfunction "IO,_DIFFIO_T14p_H10") (pintype "bidirectional+no_connect"))
    )
    (net (code "133") (name "unconnected-(IC8H-IO,_DIFFIO_T22n-PadG11)") (class "Default")
      (node (ref "IC8") (pin "G11") (pinfunction "IO,_DIFFIO_T22n_G11") (pintype "bidirectional+no_connect"))
    )
    (net (code "134") (name "unconnected-(IC8H-IO,_DIFFIO_T26p-PadE10)") (class "Default")
      (node (ref "IC8") (pin "E10") (pinfunction "IO,_DIFFIO_T26p_E10") (pintype "bidirectional+no_connect"))
    )
    (net (code "135") (name "unconnected-(IC8H-IO-PadE7)") (class "Default")
      (node (ref "IC8") (pin "E7") (pinfunction "IO_E7") (pintype "bidirectional+no_connect"))
    )
    (net (code "136") (name "unconnected-(IC8H-IO-PadF9)") (class "Default")
      (node (ref "IC8") (pin "F9") (pinfunction "IO_F9") (pintype "bidirectional+no_connect"))
    )
    (net (code "137") (name "unconnected-(IC8H-IO-PadG9)") (class "Default")
      (node (ref "IC8") (pin "G9") (pinfunction "IO_G9") (pintype "bidirectional+no_connect"))
    )
  )
)
